# 1_SurvBot_RCU_Power.net
KiCad netlist of a schematic drawn in Altium Designer
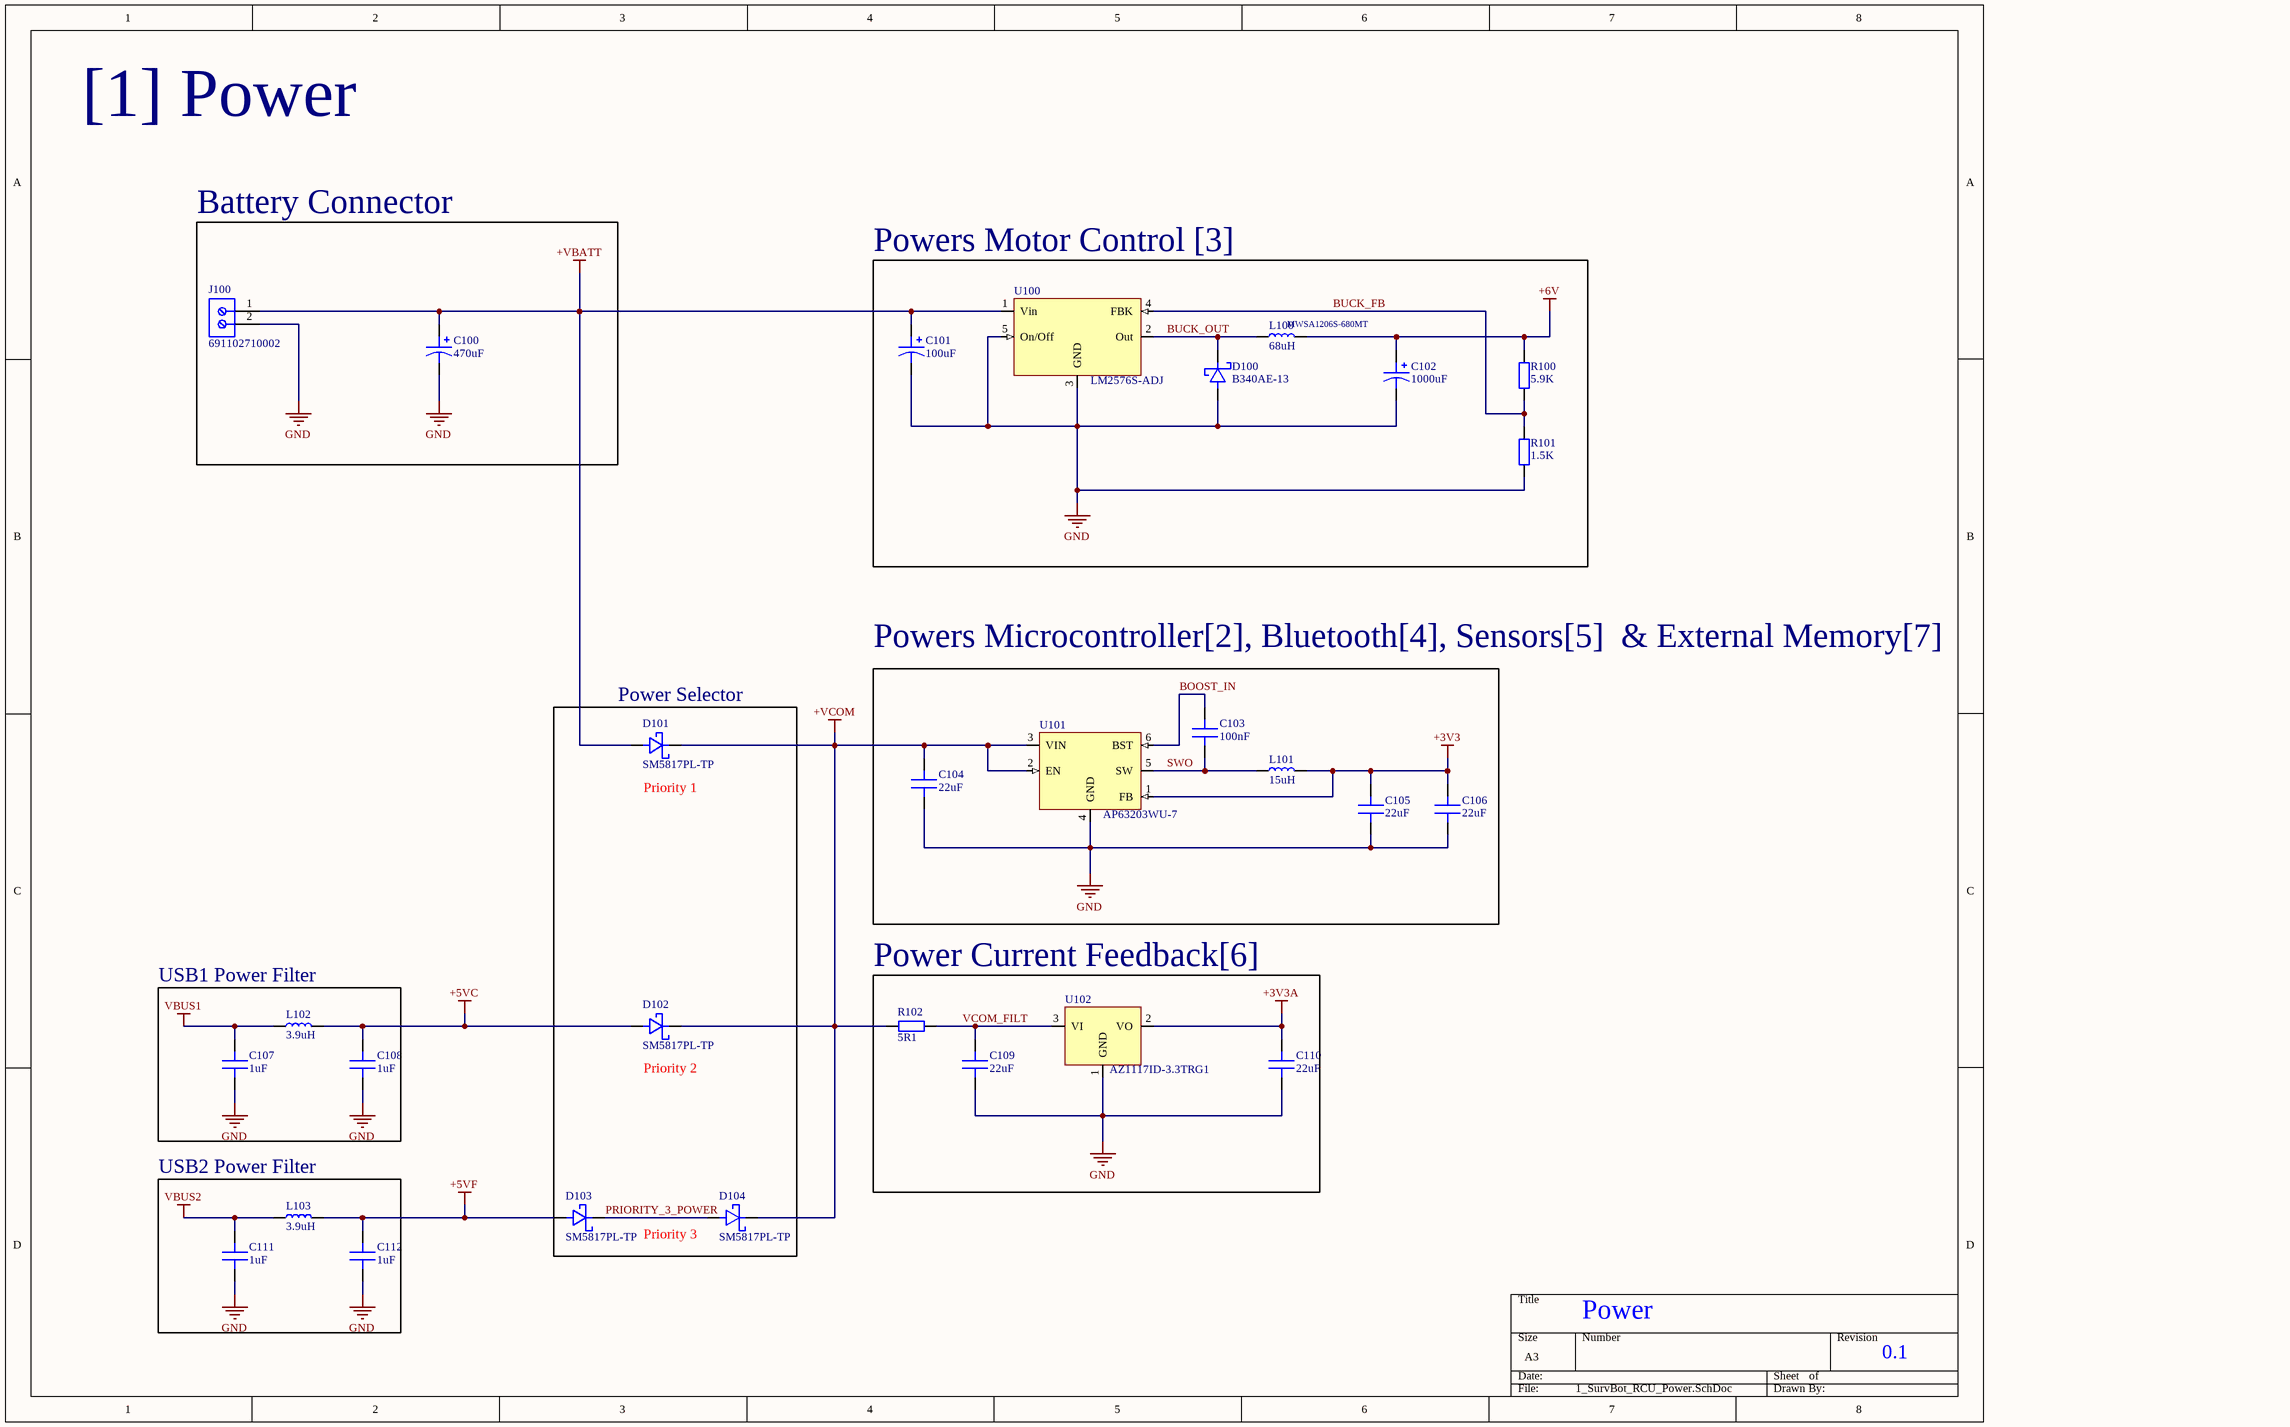
[diagram p0: 1_SurvBot_RCU_Power.SchDoc]

(export (version "E")
  (design (tool "Eeschema 10.0.6"))
  (components
    (comp (ref "C100")
      (value "470uF")
      (footprint "CAP-THT_RADIAL_D10.00mm_P5.00mm")
      (description "470 µF 35 V Aluminum Electrolytic Capacitors Radial, Can 10000 Hrs @ 105°C")
      (fields
        (field (name "MANUFACTURER") "Rubycon")
        (field (name "MANUFACTURER PART #") "35ZLH470MEFC10X16")
      )
      (libsource (lib "GhaniLibrary") (part "CAP_470uF-35V-20%-RADIAL-TH"))
    )
    (comp (ref "C101")
      (value "100uF")
      (footprint "CAP-THT-Radial__D8.0mmP3.5mm")
      (description "100 µF 50 V Aluminum Electrolytic Capacitors Radial, Can 8000 Hrs @ 105°C")
      (fields
        (field (name "MANUFACTURER") "Rubycon")
        (field (name "MANUFACTURER PART #") "50ZLH100MEFC8X11.5")
      )
      (libsource (lib "GhaniLibrary") (part "CAP_100uF-50V-20%-RADIAL-TH"))
    )
    (comp (ref "C102")
      (value "1000uF")
      (footprint "CAP-THT_RADIAL_D10.00mm_P5.00mm")
      (description "1000 µF 16 V Aluminum Electrolytic Capacitors Radial, Can 10000 Hrs @ 105°C")
      (fields
        (field (name "MANUFACTURER") "Rubycon")
        (field (name "MANUFACTURER PART #") "16ZLH1000MEFC10X16")
      )
      (libsource (lib "GhaniLibrary") (part "CAP_1000uF-16V-20%-RADIAL-TH"))
    )
    (comp (ref "C103")
      (value "100nF")
      (footprint "CAP_0603")
      (description "0.1 µF ±10% 50V Ceramic Capacitor X7R 0603 (1608 Metric)")
      (fields (field (name "MANUFACTURER") "KEMET") (field (name "MANUFACTURER PART #") "C0603C104K5RACAUTO"))
      (libsource (lib "GhaniLibrary") (part "CAP_100nF-50V-10%-0603"))
    )
    (comp (ref "C104")
      (value "22uF")
      (footprint "CAP_0603")
      (description "22 µF ±20% 10V Ceramic Capacitor X5R 0603 (1608 Metric)")
      (fields
        (field (name "MANUFACTURER") "Samsung Electro-Mechanics")
        (field (name "MANUFACTURER PART #") "CL10A226MP8NUNE")
      )
      (libsource (lib "GhaniLibrary") (part "CAP_22uF-10V-20%-0603"))
    )
    (comp (ref "C105")
      (value "22uF")
      (footprint "CAP_0603")
      (description "22 µF ±20% 10V Ceramic Capacitor X5R 0603 (1608 Metric)")
      (fields
        (field (name "MANUFACTURER") "Samsung Electro-Mechanics")
        (field (name "MANUFACTURER PART #") "CL10A226MP8NUNE")
      )
      (libsource (lib "GhaniLibrary") (part "CAP_22uF-10V-20%-0603"))
    )
    (comp (ref "C106")
      (value "22uF")
      (footprint "CAP_0603")
      (description "22 µF ±20% 10V Ceramic Capacitor X5R 0603 (1608 Metric)")
      (fields
        (field (name "MANUFACTURER") "Samsung Electro-Mechanics")
        (field (name "MANUFACTURER PART #") "CL10A226MP8NUNE")
      )
      (libsource (lib "GhaniLibrary") (part "CAP_22uF-10V-20%-0603"))
    )
    (comp (ref "C107")
      (value "1uF")
      (footprint "CAP_0603")
      (description "1 µF ±10% 16V Ceramic Capacitor X7R 0603 (1608 Metric)")
      (fields (field (name "MANUFACTURER") "YAGEO") (field (name "MANUFACTURER PART #") "CC0603KRX7R7BB105"))
      (libsource (lib "GhaniLibrary") (part "CAP_1uF-16V-10%-0603"))
    )
    (comp (ref "C108")
      (value "1uF")
      (footprint "CAP_0603")
      (description "1 µF ±10% 16V Ceramic Capacitor X7R 0603 (1608 Metric)")
      (fields (field (name "MANUFACTURER") "YAGEO") (field (name "MANUFACTURER PART #") "CC0603KRX7R7BB105"))
      (libsource (lib "GhaniLibrary") (part "CAP_1uF-16V-10%-0603"))
    )
    (comp (ref "C109")
      (value "22uF")
      (footprint "CAP_0603")
      (description "22 µF ±20% 10V Ceramic Capacitor X5R 0603 (1608 Metric)")
      (fields
        (field (name "MANUFACTURER") "Samsung Electro-Mechanics")
        (field (name "MANUFACTURER PART #") "CL10A226MP8NUNE")
      )
      (libsource (lib "GhaniLibrary") (part "CAP_22uF-10V-20%-0603"))
    )
    (comp (ref "C110")
      (value "22uF")
      (footprint "CAP_0603")
      (description "22 µF ±20% 10V Ceramic Capacitor X5R 0603 (1608 Metric)")
      (fields
        (field (name "MANUFACTURER") "Samsung Electro-Mechanics")
        (field (name "MANUFACTURER PART #") "CL10A226MP8NUNE")
      )
      (libsource (lib "GhaniLibrary") (part "CAP_22uF-10V-20%-0603"))
    )
    (comp (ref "C111")
      (value "1uF")
      (footprint "CAP_0603")
      (description "1 µF ±10% 16V Ceramic Capacitor X7R 0603 (1608 Metric)")
      (fields (field (name "MANUFACTURER") "YAGEO") (field (name "MANUFACTURER PART #") "CC0603KRX7R7BB105"))
      (libsource (lib "GhaniLibrary") (part "CAP_1uF-16V-10%-0603"))
    )
    (comp (ref "C112")
      (value "1uF")
      (footprint "CAP_0603")
      (description "1 µF ±10% 16V Ceramic Capacitor X7R 0603 (1608 Metric)")
      (fields (field (name "MANUFACTURER") "YAGEO") (field (name "MANUFACTURER PART #") "CC0603KRX7R7BB105"))
      (libsource (lib "GhaniLibrary") (part "CAP_1uF-16V-10%-0603"))
    )
    (comp (ref "D100")
      (value "B340AE-13")
      (footprint "DO-214AC, SMA")
      (description "Diode 40 V 3A Surface Mount SMA")
      (fields (field (name "MANUFACTURER") "DIODES INCORPORATED"))
      (libsource (lib "GhaniLibrary") (part "DIO-S_0.5V-40V-3A-SMA"))
    )
    (comp (ref "D101")
      (value "SM5817PL-TP")
      (footprint "DIO-SOD-123FL")
      (description "Diode 20 V 1A Surface Mount SOD-123FL")
      (fields (field (name "MANUFACTURER") "MCC(Micro Commercial Components)"))
      (libsource (lib "GhaniLibrary") (part "DIO-S_0.45V-20V-1A-SOD-123FL"))
    )
    (comp (ref "D102")
      (value "SM5817PL-TP")
      (footprint "DIO-SOD-123FL")
      (description "Diode 20 V 1A Surface Mount SOD-123FL")
      (fields (field (name "MANUFACTURER") "MCC(Micro Commercial Components)"))
      (libsource (lib "GhaniLibrary") (part "DIO-S_0.45V-20V-1A-SOD-123FL"))
    )
    (comp (ref "D103")
      (value "SM5817PL-TP")
      (footprint "DIO-SOD-123FL")
      (description "Diode 20 V 1A Surface Mount SOD-123FL")
      (fields (field (name "MANUFACTURER") "MCC(Micro Commercial Components)"))
      (libsource (lib "GhaniLibrary") (part "DIO-S_0.45V-20V-1A-SOD-123FL"))
    )
    (comp (ref "D104")
      (value "SM5817PL-TP")
      (footprint "DIO-SOD-123FL")
      (description "Diode 20 V 1A Surface Mount SOD-123FL")
      (fields (field (name "MANUFACTURER") "MCC(Micro Commercial Components)"))
      (libsource (lib "GhaniLibrary") (part "DIO-S_0.45V-20V-1A-SOD-123FL"))
    )
    (comp (ref "J100")
      (value "691102710002")
      (footprint "691102710002")
      (fields (field (name "VOLTAGE") "300V"))
      (libsource (lib "Altium Content Vault") (part "TBL - 1R - 02P - Screw"))
    )
    (comp (ref "L100")
      (value "68uH")
      (footprint "IND-SMD_13.45x12.45mm")
      (description "68 µH Shielded Drum Core, Wirewound Inductor 4 A 140mOhm Max Nonstandard")
      (fields (field (name "MANUFACTURER") "Sunlord") (field (name "MANUFACTURER PART #") "MWSA1206S-680MT"))
      (libsource (lib "GhaniLibrary") (part "IND_68uH-4A-20%-SMD"))
    )
    (comp (ref "L101")
      (value "15uH")
      (footprint "IND-SMD_ 4.90x4.90mm")
      (description "15 µH Shielded Drum Core, Wirewound Inductor 1.2 A 198mOhm Max Nonstandard")
      (fields
        (field (name "MANUFACTURER") "Taiyo Yuden")
        (field (name "MANUFACTURER PART #") "NRS5020T150MMGJ")
      )
      (libsource (lib "GhaniLibrary") (part "IND_15uH-1.2A-20%-SMD"))
    )
    (comp (ref "L102")
      (value "3.9uH")
      (footprint "IND_SMD-3.00MMX3.00MM")
      (description "3.9 µH Shielded Drum Core, Wirewound Inductor 1.5 A 115mOhm Max Nonstandard")
      (fields (field (name "MANUFACTURER") "Sunlord") (field (name "MANUFACTURER PART #") "SPH3015H3R9MT"))
      (libsource (lib "GhaniLibrary") (part "IND_3.9uH-2.1A-20%-SMD"))
    )
    (comp (ref "L103")
      (value "3.9uH")
      (footprint "IND_SMD-3.00MMX3.00MM")
      (description "3.9 µH Shielded Drum Core, Wirewound Inductor 1.5 A 115mOhm Max Nonstandard")
      (fields (field (name "MANUFACTURER") "Sunlord") (field (name "MANUFACTURER PART #") "SPH3015H3R9MT"))
      (libsource (lib "GhaniLibrary") (part "IND_3.9uH-2.1A-20%-SMD"))
    )
    (comp (ref "R100")
      (value "5.9K")
      (footprint "RES_0603")
      (description "RES 5.9K OHM 1% 100mW SMD-0603 Thick film Resistor")
      (fields (field (name "MANUFACTURER") "PANASONIC") (field (name "MANUFACTURER PART #") "ERJ3EKF5901V"))
      (libsource (lib "GhaniLibrary") (part "RES_5.9K-100mW-1%-0603"))
    )
    (comp (ref "R101")
      (value "1.5K")
      (footprint "RES_0603")
      (description "RES 1.5K OHM 1% 250mW SMD-0603 Thick film Resistor")
      (fields (field (name "MANUFACTURER") "PANASONIC") (field (name "MANUFACTURER PART #") "ERJPA3F1501V"))
      (libsource (lib "GhaniLibrary") (part "RES_1.5K-250mW-1%-0603"))
    )
    (comp (ref "R102")
      (value "5R1")
      (footprint "RES_1206")
      (description "600mW Thick Film Resistors 200V ±5% ±400ppm/℃ 5.1Ω 1206 Chip Resistor - Surface Mount")
      (fields
        (field (name "MANUFACTURER") "UNI-ROYAL(Uniroyal Elec)")
        (field (name "MANUFACTURER PART #") "AS0606J051JT5E")
      )
      (libsource (lib "GhaniLibrary") (part "RES_5R1-600mW-5%-1206"))
    )
    (comp (ref "U100")
      (value "LM2576S-ADJ")
      (footprint "TO-263-6, D2PAK (5 Leads + Tab), TO-263BA")
      (fields (field (name "MANUFACTURER") "UMW(Youtai Semiconductor Co., Ltd.)"))
      (libsource (lib "GhaniLibrary") (part "LM2576S-ADJ"))
    )
    (comp (ref "U101")
      (value "AP63203WU-7")
      (footprint "SOT-23-6 Thin, TSOT-23-6")
      (description "Buck Switching Regulator IC Positive Fixed 3.3V 1 Output 2A SOT-23-6 Thin, TSOT-23-6")
      (fields (field (name "MANUFACTURER") "Diodes Incorporated"))
      (libsource (lib "GhaniLibrary") (part "AP63203WU-7 TSOT-23-6"))
    )
    (comp (ref "U102")
      (value "AZ1117ID-3.3TRG1")
      (footprint "TO-252-3, DPAK (2 Leads + Tab), SC-63")
      (description "Linear Voltage Regulator IC Positive Fixed 1 Output 1A TO-252-3")
      (fields (field (name "MANUFACTURER") "Diodes Incorporated"))
      (libsource (lib "GhaniLibrary") (part "AZ1117ID-3.3TRG1"))
    )
  )
  (nets
    (net (code "1") (name "+3V3") (class "Default")
      (node (ref "C105") (pin "2") (pinfunction "0_2") (pintype "passive"))
      (node (ref "C106") (pin "2") (pinfunction "0_2") (pintype "passive"))
      (node (ref "L101") (pin "2") (pinfunction "2_2") (pintype "passive"))
      (node (ref "U101") (pin "1") (pinfunction "FB_1") (pintype "input"))
    )
    (net (code "2") (name "+3V3A") (class "Default")
      (node (ref "C110") (pin "2") (pinfunction "0_2") (pintype "passive"))
      (node (ref "U102") (pin "2") (pinfunction "VO_2") (pintype "power_in"))
    )
    (net (code "3") (name "+5VC") (class "Default")
      (node (ref "C108") (pin "2") (pinfunction "0_2") (pintype "passive"))
      (node (ref "D102") (pin "A") (pinfunction "1_A") (pintype "passive"))
      (node (ref "L102") (pin "2") (pinfunction "2_2") (pintype "passive"))
    )
    (net (code "4") (name "+5VF") (class "Default")
      (node (ref "C112") (pin "2") (pinfunction "0_2") (pintype "passive"))
      (node (ref "D103") (pin "A") (pinfunction "1_A") (pintype "passive"))
      (node (ref "L103") (pin "2") (pinfunction "2_2") (pintype "passive"))
    )
    (net (code "5") (name "+6V") (class "Default")
      (node (ref "C102") (pin "1") (pinfunction "0_1") (pintype "passive"))
      (node (ref "L100") (pin "2") (pinfunction "2_2") (pintype "passive"))
      (node (ref "R100") (pin "2") (pinfunction "2_2") (pintype "passive"))
    )
    (net (code "6") (name "+VBATT") (class "Default")
      (node (ref "C100") (pin "1") (pinfunction "0_1") (pintype "passive"))
      (node (ref "C101") (pin "1") (pinfunction "0_1") (pintype "passive"))
      (node (ref "D101") (pin "A") (pinfunction "1_A") (pintype "passive"))
      (node (ref "J100") (pin "1") (pinfunction "1_1") (pintype "passive"))
      (node (ref "U100") (pin "1") (pinfunction "Vin_1") (pintype "power_in"))
    )
    (net (code "7") (name "+VCOM") (class "Default")
      (node (ref "C104") (pin "2") (pinfunction "0_2") (pintype "passive"))
      (node (ref "D101") (pin "K") (pinfunction "2_K") (pintype "passive"))
      (node (ref "D102") (pin "K") (pinfunction "2_K") (pintype "passive"))
      (node (ref "D104") (pin "K") (pinfunction "2_K") (pintype "passive"))
      (node (ref "R102") (pin "1") (pinfunction "1_1") (pintype "passive"))
      (node (ref "U101") (pin "2") (pinfunction "EN_2") (pintype "input"))
      (node (ref "U101") (pin "3") (pinfunction "VIN_3") (pintype "power_in"))
    )
    (net (code "8") (name "/BOOST_IN") (class "Default")
      (node (ref "C103") (pin "2") (pinfunction "0_2") (pintype "passive"))
      (node (ref "U101") (pin "6") (pinfunction "BST_6") (pintype "input"))
    )
    (net (code "9") (name "/BUCK_FB") (class "Default")
      (node (ref "R100") (pin "1") (pinfunction "1_1") (pintype "passive"))
      (node (ref "R101") (pin "2") (pinfunction "2_2") (pintype "passive"))
      (node (ref "U100") (pin "4") (pinfunction "FBK_4") (pintype "input"))
    )
    (net (code "10") (name "/BUCK_OUT") (class "Default")
      (node (ref "D100") (pin "K") (pinfunction "2_K") (pintype "passive"))
      (node (ref "L100") (pin "1") (pinfunction "1_1") (pintype "passive"))
      (node (ref "U100") (pin "2") (pinfunction "Out_2") (pintype "power_in"))
    )
    (net (code "11") (name "/PRIORITY_3_POWER") (class "Default")
      (node (ref "D103") (pin "K") (pinfunction "2_K") (pintype "passive"))
      (node (ref "D104") (pin "A") (pinfunction "1_A") (pintype "passive"))
    )
    (net (code "12") (name "/SWO") (class "Default")
      (node (ref "C103") (pin "1") (pinfunction "0_1") (pintype "passive"))
      (node (ref "L101") (pin "1") (pinfunction "1_1") (pintype "passive"))
      (node (ref "U101") (pin "5") (pinfunction "SW_5") (pintype "power_in"))
    )
    (net (code "13") (name "/VCOM_FILT") (class "Default")
      (node (ref "C109") (pin "2") (pinfunction "0_2") (pintype "passive"))
      (node (ref "R102") (pin "2") (pinfunction "2_2") (pintype "passive"))
      (node (ref "U102") (pin "3") (pinfunction "VI_3") (pintype "power_in"))
    )
    (net (code "14") (name "GND") (class "Default")
      (node (ref "C100") (pin "2") (pinfunction "0_2") (pintype "passive"))
      (node (ref "C101") (pin "2") (pinfunction "0_2") (pintype "passive"))
      (node (ref "C102") (pin "2") (pinfunction "0_2") (pintype "passive"))
      (node (ref "C104") (pin "1") (pinfunction "0_1") (pintype "passive"))
      (node (ref "C105") (pin "1") (pinfunction "0_1") (pintype "passive"))
      (node (ref "C106") (pin "1") (pinfunction "0_1") (pintype "passive"))
      (node (ref "C107") (pin "1") (pinfunction "0_1") (pintype "passive"))
      (node (ref "C108") (pin "1") (pinfunction "0_1") (pintype "passive"))
      (node (ref "C109") (pin "1") (pinfunction "0_1") (pintype "passive"))
      (node (ref "C110") (pin "1") (pinfunction "0_1") (pintype "passive"))
      (node (ref "C111") (pin "1") (pinfunction "0_1") (pintype "passive"))
      (node (ref "C112") (pin "1") (pinfunction "0_1") (pintype "passive"))
      (node (ref "D100") (pin "A") (pinfunction "1_A") (pintype "passive"))
      (node (ref "J100") (pin "2") (pinfunction "2_2") (pintype "passive"))
      (node (ref "R101") (pin "1") (pinfunction "1_1") (pintype "passive"))
      (node (ref "U100") (pin "3") (pinfunction "GND_3") (pintype "power_in"))
      (node (ref "U100") (pin "5") (pinfunction "On/Off_5") (pintype "input"))
      (node (ref "U101") (pin "4") (pinfunction "GND_4") (pintype "power_in"))
      (node (ref "U102") (pin "1") (pinfunction "GND_1") (pintype "power_in"))
    )
    (net (code "15") (name "VBUS1") (class "Default")
      (node (ref "C107") (pin "2") (pinfunction "0_2") (pintype "passive"))
      (node (ref "L102") (pin "1") (pinfunction "1_1") (pintype "passive"))
    )
    (net (code "16") (name "VBUS2") (class "Default")
      (node (ref "C111") (pin "2") (pinfunction "0_2") (pintype "passive"))
      (node (ref "L103") (pin "1") (pinfunction "1_1") (pintype "passive"))
    )
  )
)
